# v1_1.net
KiCad netlist of a schematic drawn in Altium Designer
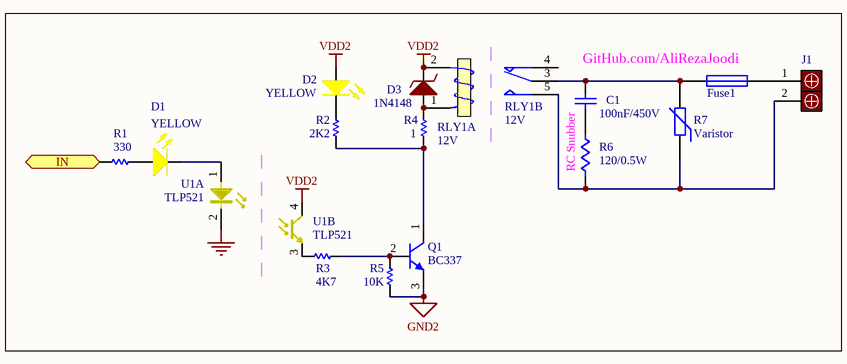
[diagram p0: v1.1.SchDoc]

(export (version "E")
  (design (tool "Eeschema 10.0.6"))
  (components
    (comp (ref "C1")
      (value "100nF/450V")
      (footprint "C_THD_CER_(P2.54-D3.5-T1.5)")
      (description "Capacitor, Ceramic Multilayer")
      (libsource (lib "Passive") (part "Capacitor_Ceramic"))
    )
    (comp (ref "D1")
      (value "YELLOW")
      (footprint "LED_THD_3MM_YELLOW_R")
      (description "LED, Yellow")
      (fields (field (name "MANUFACTURER") "Generic Components") (field (name "PUBLISHER") "Altium Limited"))
      (libsource (lib "Display") (part "LED_YELLOW"))
    )
    (comp (ref "D2")
      (value "YELLOW")
      (footprint "LED_THD_3MM_YELLOW_R")
      (description "LED, Yellow")
      (fields (field (name "MANUFACTURER") "Generic Components") (field (name "PUBLISHER") "Altium Limited"))
      (libsource (lib "Display") (part "LED_YELLOW"))
    )
    (comp (ref "D3")
      (value "1N4148")
      (footprint "D_THD_AXIAL0.3_DO-35")
      (description "Diode, Zener")
      (libsource (lib "Passive") (part "Diode_Zener"))
    )
    (comp (ref "Fuse1")
      (value "2A")
      (footprint "PIN-W2/E2.8")
      (description "Fuse")
      (fields (field (name "MANUFACTURER") "Generic Components") (field (name "PUBLISHER") "Altium Limited"))
      (libsource (lib "Miscellaneous Devices") (part "Fuse 1"))
    )
    (comp (ref "J1")
      (value "2PIN")
      (footprint "Connector_Phoenix_2PIN_MSTB")
      (description "Connector, Header, 2Pin")
      (libsource (lib "Connector") (part "Connector1x2_Power"))
    )
    (comp (ref "Q1")
      (value "BC337")
      (footprint "TO92C")
      (description "NPN Bipolar Transistor")
      (fields (field (name "MANUFACTURER") "Generic Components") (field (name "PUBLISHER") "Altium Limited"))
      (libsource (lib "Miscellaneous Devices") (part "NPN"))
    )
    (comp (ref "R1")
      (value "330")
      (footprint "R_THD_AXIAL0.4(1/4W)")
      (description "Resistor")
      (libsource (lib "Passive") (part "Resistor"))
    )
    (comp (ref "R2")
      (value "2K2")
      (footprint "R_THD_AXIAL0.4(1/4W)")
      (description "Resistor")
      (libsource (lib "Passive") (part "Resistor"))
    )
    (comp (ref "R3")
      (value "4K7")
      (footprint "R_THD_AXIAL0.4(1/4W)")
      (description "Resistor")
      (libsource (lib "Passive") (part "Resistor"))
    )
    (comp (ref "R4")
      (value "1")
      (footprint "R_THD_AXIAL0.4(1/4W)")
      (description "Resistor")
      (libsource (lib "Passive") (part "Resistor"))
    )
    (comp (ref "R5")
      (value "10K")
      (footprint "R_THD_AXIAL0.4(1/4W)")
      (description "Resistor")
      (libsource (lib "Passive") (part "Resistor"))
    )
    (comp (ref "R6")
      (value "120/0.5W")
      (footprint "R_THD_AXIAL0.4(1/4W)")
      (description "Resistor")
      (libsource (lib "Passive") (part "Resistor_3Form"))
    )
    (comp (ref "R7")
      (value "Varistor")
      (footprint "R2012-0805")
      (description "Varistor (Voltage-Sensitive Resistor)")
      (fields (field (name "MANUFACTURER") "Generic Components") (field (name "PUBLISHER") "Altium Limited"))
      (libsource (lib "Miscellaneous Devices") (part "Res Varistor"))
    )
    (comp (ref "RLY1")
      (value "12V")
      (footprint "RELAY_SPDT_5PIN_2216")
      (description "SPDT Relay")
      (libsource (lib "Passive") (part "Relay_SPDT_2Form"))
    )
    (comp (ref "U1")
      (value "TLP521")
      (footprint "DIP_4")
      (description "Optoisolator")
      (fields (field (name "PUBLISHER") "Altium Limited"))
      (libsource (lib "IC") (part "Optoisolator"))
    )
  )
  (nets
    (net (code "1") (name "/IN") (class "Default")
      (node (ref "R1") (pin "2") (pinfunction "2_2") (pintype "passive"))
    )
    (net (code "2") (name "GND") (class "Default")
      (node (ref "U1") (pin "2") (pinfunction "K_2") (pintype "power_in"))
    )
    (net (code "3") (name "GND2") (class "Default")
      (node (ref "Q1") (pin "3") (pinfunction "E_3") (pintype "passive"))
      (node (ref "R5") (pin "2") (pinfunction "2_2") (pintype "passive"))
    )
    (net (code "4") (name "Net-(C1-Pad1)") (class "Default")
      (node (ref "C1") (pin "1") (pinfunction "1_1") (pintype "passive"))
      (node (ref "R6") (pin "2") (pinfunction "2_2") (pintype "passive"))
    )
    (net (code "5") (name "Net-(D1-A)") (class "Default")
      (node (ref "D1") (pin "1") (pinfunction "A_1") (pintype "passive"))
      (node (ref "R1") (pin "1") (pinfunction "1_1") (pintype "passive"))
    )
    (net (code "6") (name "Net-(D1-K)") (class "Default")
      (node (ref "D1") (pin "2") (pinfunction "K_2") (pintype "passive"))
      (node (ref "U1") (pin "1") (pinfunction "A_1") (pintype "power_in"))
    )
    (net (code "7") (name "Net-(D2-K)") (class "Default")
      (node (ref "D2") (pin "2") (pinfunction "K_2") (pintype "passive"))
      (node (ref "R2") (pin "2") (pinfunction "2_2") (pintype "passive"))
    )
    (net (code "8") (name "Net-(Fuse1-Pad2)") (class "Default")
      (node (ref "Fuse1") (pin "2") (pinfunction "2_2") (pintype "passive"))
      (node (ref "J1") (pin "1") (pinfunction "1_1") (pintype "passive"))
    )
    (net (code "9") (name "Net-(Q1-B)") (class "Default")
      (node (ref "Q1") (pin "2") (pinfunction "B_2") (pintype "passive"))
      (node (ref "R3") (pin "1") (pinfunction "1_1") (pintype "passive"))
      (node (ref "R5") (pin "1") (pinfunction "1_1") (pintype "passive"))
    )
    (net (code "10") (name "Net-(Q1-C)") (class "Default")
      (node (ref "Q1") (pin "1") (pinfunction "C_1") (pintype "passive"))
      (node (ref "R2") (pin "1") (pinfunction "1_1") (pintype "passive"))
      (node (ref "R4") (pin "1") (pinfunction "1_1") (pintype "passive"))
    )
    (net (code "11") (name "Net-(RLY1A-T2)") (class "Default")
      (node (ref "D3") (pin "1") (pinfunction "1_1") (pintype "passive"))
      (node (ref "R4") (pin "2") (pinfunction "2_2") (pintype "passive"))
      (node (ref "RLY1") (pin "1") (pinfunction "T2_1") (pintype "passive"))
    )
    (net (code "12") (name "Net-(RLY1B-COM)") (class "Default")
      (node (ref "C1") (pin "2") (pinfunction "2_2") (pintype "passive"))
      (node (ref "Fuse1") (pin "1") (pinfunction "1_1") (pintype "passive"))
      (node (ref "R7") (pin "2") (pinfunction "2_2") (pintype "passive"))
      (node (ref "RLY1") (pin "3") (pinfunction "COM_3") (pintype "passive"))
    )
    (net (code "13") (name "Net-(RLY1B-NO)") (class "Default")
      (node (ref "J1") (pin "2") (pinfunction "2_2") (pintype "passive"))
      (node (ref "R6") (pin "1") (pinfunction "1_1") (pintype "passive"))
      (node (ref "R7") (pin "1") (pinfunction "1_1") (pintype "passive"))
      (node (ref "RLY1") (pin "5") (pinfunction "NO_5") (pintype "passive"))
    )
    (net (code "14") (name "Net-(U1B-E)") (class "Default")
      (node (ref "R3") (pin "2") (pinfunction "2_2") (pintype "passive"))
      (node (ref "U1") (pin "3") (pinfunction "E_3") (pintype "passive"))
    )
    (net (code "15") (name "VDD2") (class "Default")
      (node (ref "D2") (pin "1") (pinfunction "A_1") (pintype "passive"))
      (node (ref "D3") (pin "2") (pinfunction "2_2") (pintype "passive"))
      (node (ref "RLY1") (pin "2") (pinfunction "T1_2") (pintype "passive"))
      (node (ref "U1") (pin "4") (pinfunction "C_4") (pintype "passive"))
    )
    (net (code "16") (name "unconnected-(RLY1B-NC-Pad4)") (class "Default")
      (node (ref "RLY1") (pin "4") (pinfunction "NC_4") (pintype "passive"))
    )
  )
)
